# FM-Radio_180828.net
KiCad netlist of a schematic drawn in EAGLE
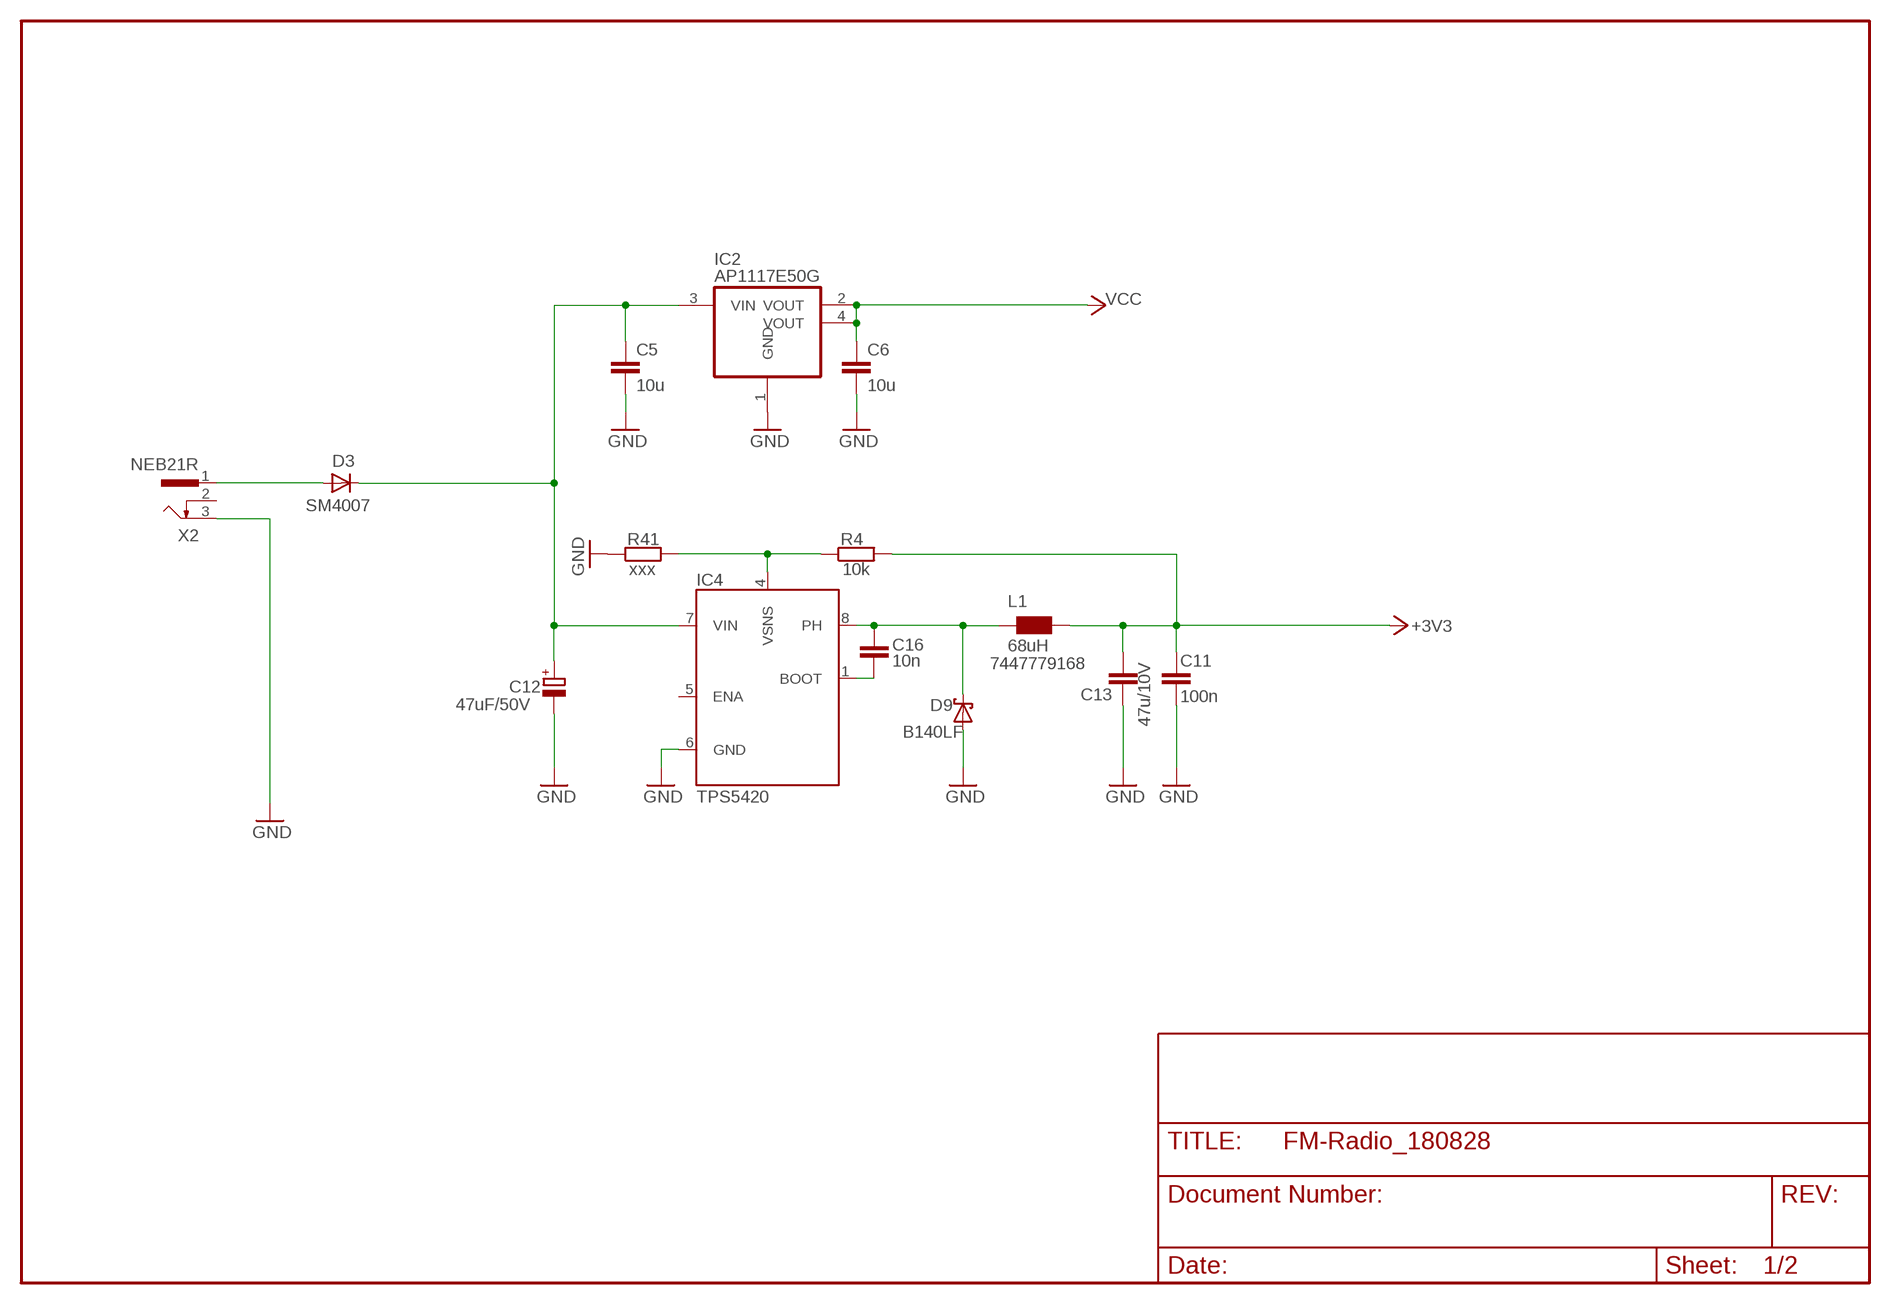
[diagram p0: schematic, sheet 1]
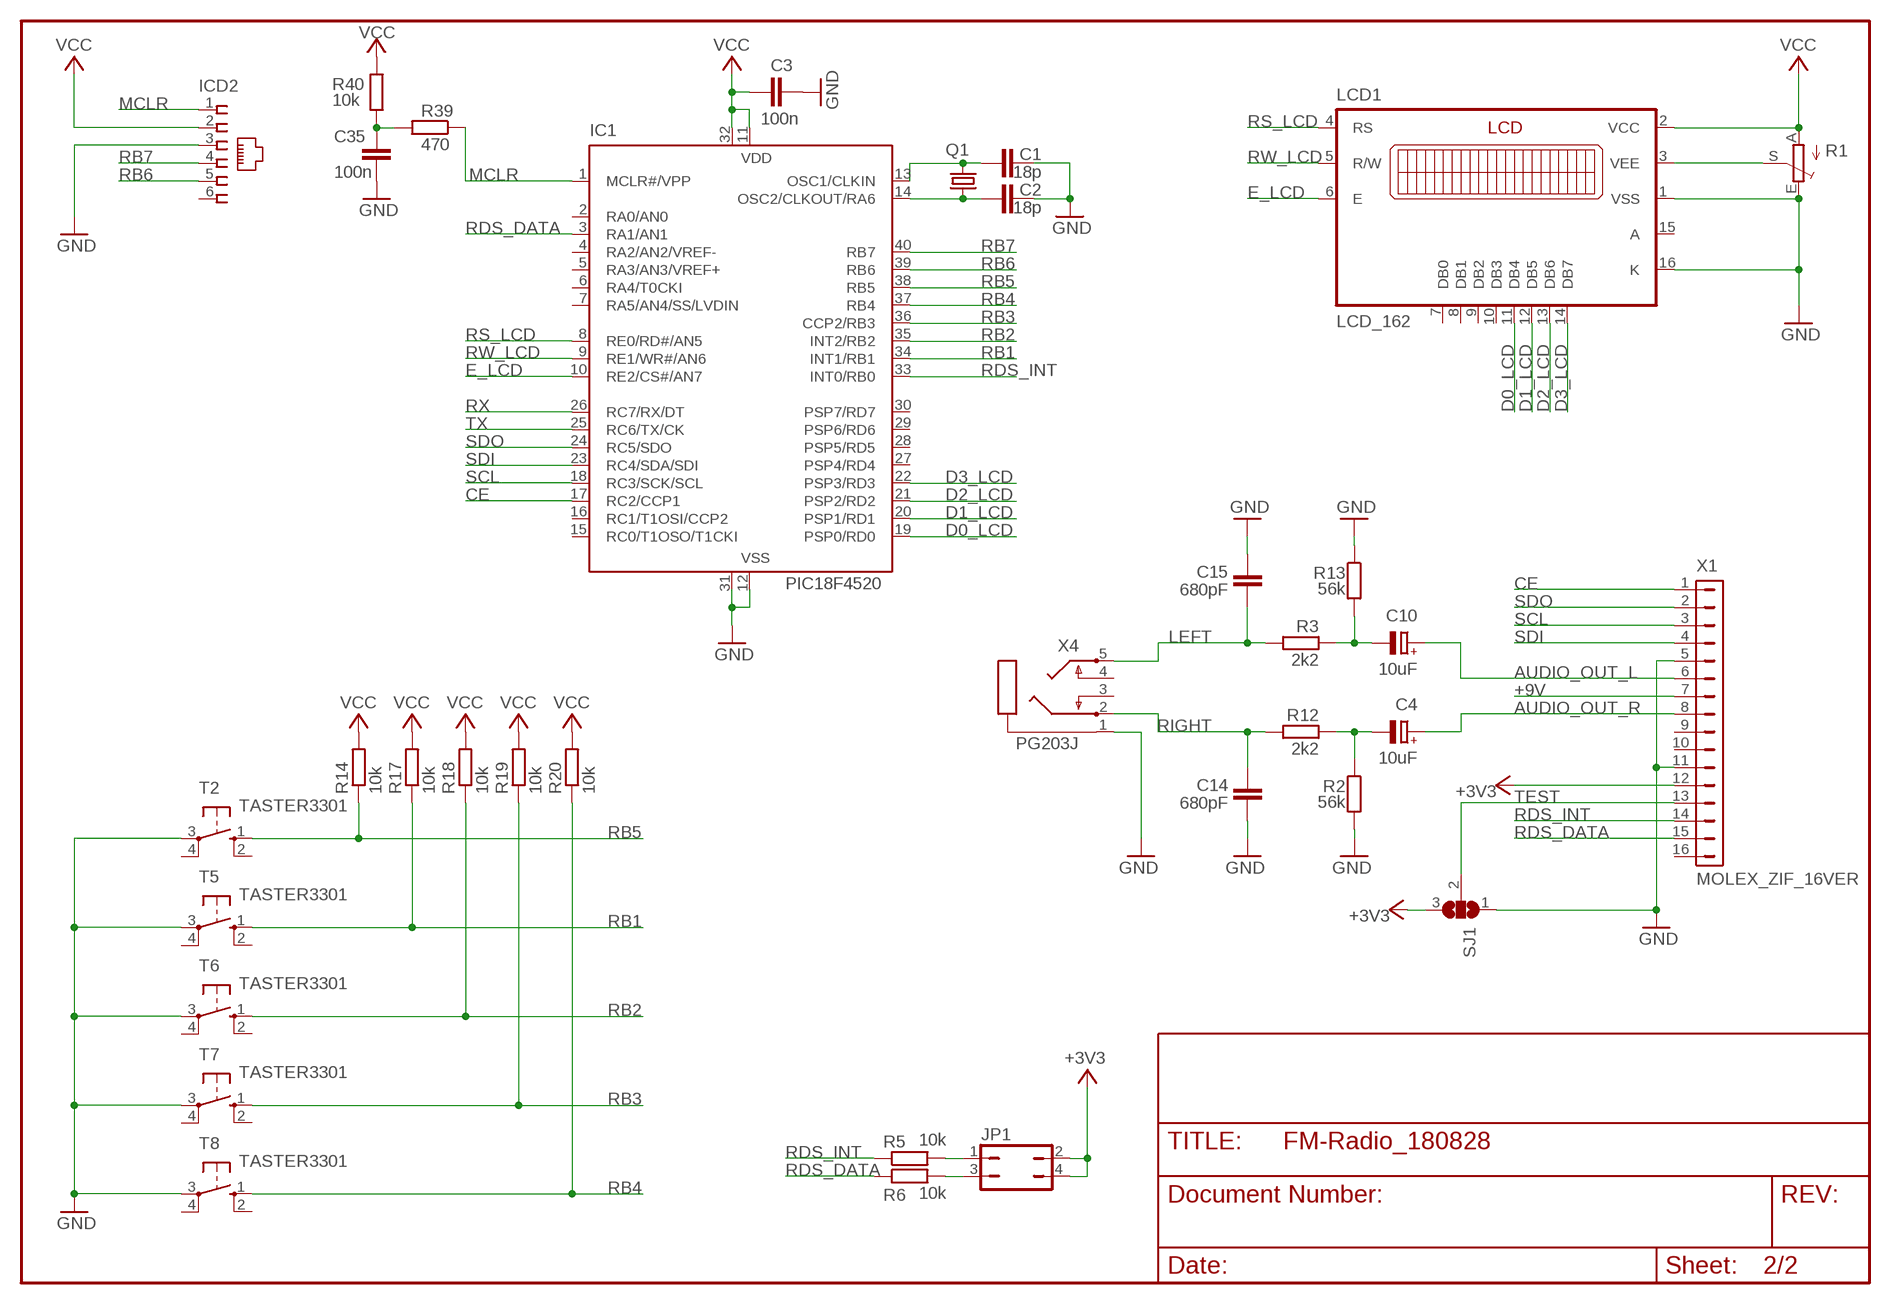
[diagram p1: schematic, sheet 2]

(export (version "E")
  (design (tool "Eeschema 10.0.6"))
  (components
    (comp (ref "C1")
      (value "18p")
      (footprint "eagle-import:C0805")
      (libsource (lib "eagle-import") (part "C-EUC0805"))
    )
    (comp (ref "C2")
      (value "18p")
      (footprint "eagle-import:C0805")
      (libsource (lib "eagle-import") (part "C-EUC0805"))
    )
    (comp (ref "C3")
      (value "100n")
      (footprint "eagle-import:C0805")
      (libsource (lib "eagle-import") (part "C-EUC0805"))
    )
    (comp (ref "C4")
      (value "10uF")
      (footprint "eagle-import:TT2D4")
      (libsource (lib "eagle-import") (part "CPOL-EUTT2D4"))
    )
    (comp (ref "C10")
      (value "10uF")
      (footprint "eagle-import:TT2D4")
      (libsource (lib "eagle-import") (part "CPOL-EUTT2D4"))
    )
    (comp (ref "C14")
      (value "680pF")
      (footprint "eagle-import:C025-025X050")
      (libsource (lib "eagle-import") (part "C-EU025-025X050"))
    )
    (comp (ref "C15")
      (value "680pF")
      (footprint "eagle-import:C025-025X050")
      (libsource (lib "eagle-import") (part "C-EU025-025X050"))
    )
    (comp (ref "C35")
      (value "100n")
      (footprint "eagle-import:C0805")
      (libsource (lib "eagle-import") (part "C-EUC0805"))
    )
    (comp (ref "IC1")
      (value "PIC18F4520")
      (footprint "eagle-import:DIL40")
      (libsource (lib "eagle-import") (part "PIC18C4X2"))
    )
    (comp (ref "ICD2")
      (value "520250-3")
      (footprint "eagle-import:520250-3")
      (libsource (lib "eagle-import") (part "520250-3"))
    )
    (comp (ref "JP1")
      (value "JP2Q")
      (footprint "eagle-import:JP2Q")
      (libsource (lib "eagle-import") (part "JP2Q"))
    )
    (comp (ref "LCD1")
      (value "LCD_162")
      (footprint "eagle-import:LCD_162")
      (libsource (lib "eagle-import") (part "LCD_162"))
    )
    (comp (ref "Q1")
      (value "CRYTALHC49U-V")
      (footprint "eagle-import:HC49U-V")
      (libsource (lib "eagle-import") (part "CRYTALHC49U-V"))
    )
    (comp (ref "R1")
      (value "TRIM_EU-LI10")
      (footprint "eagle-import:LI10")
      (libsource (lib "eagle-import") (part "TRIM_EU-LI10"))
    )
    (comp (ref "R2")
      (value "56k")
      (footprint "eagle-import:0207_7")
      (libsource (lib "eagle-import") (part "R-EU_0207/7"))
    )
    (comp (ref "R3")
      (value "2k2")
      (footprint "eagle-import:0207_7")
      (libsource (lib "eagle-import") (part "R-EU_0207/7"))
    )
    (comp (ref "R5")
      (value "10k")
      (footprint "eagle-import:M0805")
      (libsource (lib "eagle-import") (part "rcl_416_R-EU_M0805"))
    )
    (comp (ref "R6")
      (value "10k")
      (footprint "eagle-import:M0805")
      (libsource (lib "eagle-import") (part "rcl_416_R-EU_M0805"))
    )
    (comp (ref "R12")
      (value "2k2")
      (footprint "eagle-import:0207_7")
      (libsource (lib "eagle-import") (part "R-EU_0207/7"))
    )
    (comp (ref "R13")
      (value "56k")
      (footprint "eagle-import:0207_7")
      (libsource (lib "eagle-import") (part "R-EU_0207/7"))
    )
    (comp (ref "R14")
      (value "10k")
      (footprint "eagle-import:0207_7")
      (libsource (lib "eagle-import") (part "R-EU_0207/7"))
    )
    (comp (ref "R17")
      (value "10k")
      (footprint "eagle-import:0207_7")
      (libsource (lib "eagle-import") (part "R-EU_0207/7"))
    )
    (comp (ref "R18")
      (value "10k")
      (footprint "eagle-import:0207_7")
      (libsource (lib "eagle-import") (part "R-EU_0207/7"))
    )
    (comp (ref "R19")
      (value "10k")
      (footprint "eagle-import:0207_7")
      (libsource (lib "eagle-import") (part "R-EU_0207/7"))
    )
    (comp (ref "R20")
      (value "10k")
      (footprint "eagle-import:0207_7")
      (libsource (lib "eagle-import") (part "R-EU_0207/7"))
    )
    (comp (ref "R39")
      (value "470")
      (footprint "eagle-import:M0805")
      (libsource (lib "eagle-import") (part "R-EU_M0805"))
    )
    (comp (ref "R40")
      (value "10k")
      (footprint "eagle-import:M0805")
      (libsource (lib "eagle-import") (part "R-EU_M0805"))
    )
    (comp (ref "SJ1")
      (value "SJ2W")
      (footprint "eagle-import:SJ_2")
      (libsource (lib "eagle-import") (part "SJ2W"))
    )
    (comp (ref "T2")
      (value "TASTER3301")
      (footprint "eagle-import:TASTER3301")
      (libsource (lib "eagle-import") (part "TASTER3301"))
    )
    (comp (ref "T5")
      (value "TASTER3301")
      (footprint "eagle-import:TASTER3301")
      (libsource (lib "eagle-import") (part "TASTER3301"))
    )
    (comp (ref "T6")
      (value "TASTER3301")
      (footprint "eagle-import:TASTER3301")
      (libsource (lib "eagle-import") (part "TASTER3301"))
    )
    (comp (ref "T7")
      (value "TASTER3301")
      (footprint "eagle-import:TASTER3301")
      (libsource (lib "eagle-import") (part "TASTER3301"))
    )
    (comp (ref "T8")
      (value "TASTER3301")
      (footprint "eagle-import:TASTER3301")
      (libsource (lib "eagle-import") (part "TASTER3301"))
    )
    (comp (ref "X1")
      (value "MOLEX_ZIF_16VER")
      (footprint "eagle-import:ZIF_16POL")
      (libsource (lib "eagle-import") (part "MOLEX_ZIF_16VER"))
    )
    (comp (ref "X4")
      (value "PG203J")
      (footprint "eagle-import:PG203J")
      (libsource (lib "eagle-import") (part "PG203J"))
    )
    (comp (ref "C5")
      (value "10u")
      (footprint "eagle-import:C0805")
      (libsource (lib "eagle-import") (part "C-EUC0805"))
    )
    (comp (ref "C6")
      (value "10u")
      (footprint "eagle-import:C0805")
      (libsource (lib "eagle-import") (part "C-EUC0805"))
    )
    (comp (ref "C11")
      (value "100n")
      (footprint "eagle-import:C0805")
      (libsource (lib "eagle-import") (part "rcl_416_C-EUC0805"))
    )
    (comp (ref "C12")
      (value "47uF/50V")
      (footprint "eagle-import:PANASONIC_D")
      (libsource (lib "eagle-import") (part "rcl_416_CPOL-EUD"))
    )
    (comp (ref "C13")
      (value "47u/10V")
      (footprint "eagle-import:C1210")
      (libsource (lib "eagle-import") (part "C-EUC1210"))
    )
    (comp (ref "C16")
      (value "10n")
      (footprint "eagle-import:C0805")
      (libsource (lib "eagle-import") (part "rcl_416_C-EUC0805"))
    )
    (comp (ref "D3")
      (value "SM4007")
      (footprint "eagle-import:MELF")
      (libsource (lib "eagle-import") (part "DIODE_MELF"))
    )
    (comp (ref "D9")
      (value "B140LF")
      (footprint "eagle-import:CD1607")
      (libsource (lib "eagle-import") (part "SCHOTTKY_CD1607"))
    )
    (comp (ref "IC2")
      (value "AP1117E50G")
      (footprint "eagle-import:SOT223")
      (libsource (lib "eagle-import") (part "REG1117-2OUT"))
    )
    (comp (ref "IC4")
      (value "TPS5420")
      (footprint "eagle-import:SO8")
      (libsource (lib "eagle-import") (part "TPS5410"))
    )
    (comp (ref "L1")
      (value "68uH")
      (footprint "eagle-import:WE-PD_S_M")
      (libsource (lib "eagle-import") (part "WE-PD_S/M"))
    )
    (comp (ref "R4")
      (value "10k")
      (footprint "eagle-import:R0805")
      (libsource (lib "eagle-import") (part "R-EU_R0805"))
    )
    (comp (ref "R41")
      (value "xxx")
      (footprint "eagle-import:R0805")
      (libsource (lib "eagle-import") (part "R-EU_R0805"))
    )
    (comp (ref "X2")
      (value "NEB21R")
      (footprint "eagle-import:NEB21R")
      (fields (field (name "MPN") "NEB 21 R"))
      (libsource (lib "eagle-import") (part "NEB21R"))
    )
  )
  (nets
    (net (code "1") (name "+3V3") (class "Default")
      (node (ref "C11") (pin "1") (pinfunction "1_1") (pintype "passive"))
      (node (ref "C13") (pin "1") (pinfunction "1_1") (pintype "passive"))
      (node (ref "JP1") (pin "2") (pinfunction "2_2") (pintype "passive"))
      (node (ref "JP1") (pin "4") (pinfunction "4_4") (pintype "passive"))
      (node (ref "L1") (pin "1") (pinfunction "2_1") (pintype "passive"))
      (node (ref "R4") (pin "2") (pinfunction "2_2") (pintype "passive"))
      (node (ref "SJ1") (pin "3") (pinfunction "3_3") (pintype "passive"))
      (node (ref "X1") (pin "12") (pinfunction "12_12") (pintype "passive"))
    )
    (net (code "2") (name "+9V") (class "Default")
      (node (ref "C12") (pin "+") (pinfunction "+_+") (pintype "passive"))
      (node (ref "C5") (pin "1") (pinfunction "1_1") (pintype "passive"))
      (node (ref "D3") (pin "C") (pinfunction "C_C") (pintype "passive"))
      (node (ref "IC2") (pin "3") (pinfunction "VIN_3") (pintype "input"))
      (node (ref "IC4") (pin "7") (pinfunction "VIN_7") (pintype "bidirectional"))
      (node (ref "X1") (pin "7") (pinfunction "7_7") (pintype "passive"))
    )
    (net (code "3") (name "AUDIO_OUT_L") (class "Default")
      (node (ref "C10") (pin "+") (pinfunction "+_+") (pintype "passive"))
      (node (ref "X1") (pin "6") (pinfunction "6_6") (pintype "passive"))
    )
    (net (code "4") (name "AUDIO_OUT_R") (class "Default")
      (node (ref "C4") (pin "+") (pinfunction "+_+") (pintype "passive"))
      (node (ref "X1") (pin "8") (pinfunction "8_8") (pintype "passive"))
    )
    (net (code "5") (name "CE") (class "Default")
      (node (ref "IC1") (pin "17") (pinfunction "RC2/CCP1_17") (pintype "bidirectional"))
      (node (ref "X1") (pin "1") (pinfunction "1_1") (pintype "passive"))
    )
    (net (code "6") (name "D0_LCD") (class "Default")
      (node (ref "IC1") (pin "19") (pinfunction "PSP0/RD0_19") (pintype "bidirectional"))
      (node (ref "LCD1") (pin "11") (pinfunction "DB4_11") (pintype "passive"))
    )
    (net (code "7") (name "D1_LCD") (class "Default")
      (node (ref "IC1") (pin "20") (pinfunction "PSP1/RD1_20") (pintype "bidirectional"))
      (node (ref "LCD1") (pin "12") (pinfunction "DB5_12") (pintype "passive"))
    )
    (net (code "8") (name "D2_LCD") (class "Default")
      (node (ref "IC1") (pin "21") (pinfunction "PSP2/RD2_21") (pintype "bidirectional"))
      (node (ref "LCD1") (pin "13") (pinfunction "DB6_13") (pintype "passive"))
    )
    (net (code "9") (name "D3_LCD") (class "Default")
      (node (ref "IC1") (pin "22") (pinfunction "PSP3/RD3_22") (pintype "bidirectional"))
      (node (ref "LCD1") (pin "14") (pinfunction "DB7_14") (pintype "passive"))
    )
    (net (code "10") (name "E_LCD") (class "Default")
      (node (ref "IC1") (pin "10") (pinfunction "RE2/CS#/AN7_10") (pintype "bidirectional"))
      (node (ref "LCD1") (pin "6") (pinfunction "E_6") (pintype "input"))
    )
    (net (code "11") (name "GND") (class "Default")
      (node (ref "C1") (pin "2") (pinfunction "2_2") (pintype "passive"))
      (node (ref "C11") (pin "2") (pinfunction "2_2") (pintype "passive"))
      (node (ref "C12") (pin "-") (pinfunction "-_-") (pintype "passive"))
      (node (ref "C13") (pin "2") (pinfunction "2_2") (pintype "passive"))
      (node (ref "C14") (pin "1") (pinfunction "1_1") (pintype "passive"))
      (node (ref "C15") (pin "2") (pinfunction "2_2") (pintype "passive"))
      (node (ref "C2") (pin "2") (pinfunction "2_2") (pintype "passive"))
      (node (ref "C3") (pin "2") (pinfunction "2_2") (pintype "passive"))
      (node (ref "C35") (pin "2") (pinfunction "2_2") (pintype "passive"))
      (node (ref "C5") (pin "2") (pinfunction "2_2") (pintype "passive"))
      (node (ref "C6") (pin "2") (pinfunction "2_2") (pintype "passive"))
      (node (ref "D9") (pin "A") (pinfunction "A_A") (pintype "passive"))
      (node (ref "IC1") (pin "12") (pinfunction "VSS_12") (pintype "power_in"))
      (node (ref "IC1") (pin "31") (pinfunction "VSS_31") (pintype "power_in"))
      (node (ref "IC2") (pin "1") (pinfunction "GND_1") (pintype "power_in"))
      (node (ref "IC4") (pin "6") (pinfunction "GND_6") (pintype "bidirectional"))
      (node (ref "ICD2") (pin "3") (pinfunction "3_3") (pintype "passive"))
      (node (ref "LCD1") (pin "1") (pinfunction "VSS_1") (pintype "power_in"))
      (node (ref "LCD1") (pin "16") (pinfunction "K_16") (pintype "input"))
      (node (ref "R1") (pin "E") (pinfunction "E_E") (pintype "passive"))
      (node (ref "R13") (pin "1") (pinfunction "1_1") (pintype "passive"))
      (node (ref "R2") (pin "2") (pinfunction "2_2") (pintype "passive"))
      (node (ref "R41") (pin "1") (pinfunction "1_1") (pintype "passive"))
      (node (ref "SJ1") (pin "1") (pinfunction "1_1") (pintype "passive"))
      (node (ref "T2") (pin "3") (pinfunction "P_3") (pintype "passive"))
      (node (ref "T5") (pin "3") (pinfunction "P_3") (pintype "passive"))
      (node (ref "T6") (pin "3") (pinfunction "P_3") (pintype "passive"))
      (node (ref "T7") (pin "3") (pinfunction "P_3") (pintype "passive"))
      (node (ref "T8") (pin "3") (pinfunction "P_3") (pintype "passive"))
      (node (ref "X1") (pin "11") (pinfunction "11_11") (pintype "passive"))
      (node (ref "X1") (pin "5") (pinfunction "5_5") (pintype "passive"))
      (node (ref "X2") (pin "3") (pinfunction "3_3") (pintype "passive"))
      (node (ref "X4") (pin "1") (pinfunction "1_1") (pintype "passive"))
    )
    (net (code "12") (name "LEFT") (class "Default")
      (node (ref "C15") (pin "1") (pinfunction "1_1") (pintype "passive"))
      (node (ref "R3") (pin "1") (pinfunction "1_1") (pintype "passive"))
      (node (ref "X4") (pin "5") (pinfunction "5_5") (pintype "passive"))
    )
    (net (code "13") (name "MCLR") (class "Default")
      (node (ref "IC1") (pin "1") (pinfunction "MCLR#/VPP_1") (pintype "input"))
      (node (ref "ICD2") (pin "1") (pinfunction "1_1") (pintype "passive"))
      (node (ref "R39") (pin "1") (pinfunction "1_1") (pintype "passive"))
    )
    (net (code "14") (name "Net-(C4-Pad-)") (class "Default")
      (node (ref "C4") (pin "-") (pinfunction "-_-") (pintype "passive"))
      (node (ref "R12") (pin "2") (pinfunction "2_2") (pintype "passive"))
      (node (ref "R2") (pin "1") (pinfunction "1_1") (pintype "passive"))
    )
    (net (code "15") (name "Net-(C10-Pad-)") (class "Default")
      (node (ref "C10") (pin "-") (pinfunction "-_-") (pintype "passive"))
      (node (ref "R13") (pin "2") (pinfunction "2_2") (pintype "passive"))
      (node (ref "R3") (pin "2") (pinfunction "2_2") (pintype "passive"))
    )
    (net (code "16") (name "Net-(C35-Pad1)") (class "Default")
      (node (ref "C35") (pin "1") (pinfunction "1_1") (pintype "passive"))
      (node (ref "R39") (pin "2") (pinfunction "2_2") (pintype "passive"))
      (node (ref "R40") (pin "2") (pinfunction "2_2") (pintype "passive"))
    )
    (net (code "17") (name "Net-(D3-PadA)") (class "Default")
      (node (ref "D3") (pin "A") (pinfunction "A_A") (pintype "passive"))
      (node (ref "X2") (pin "1") (pinfunction "1_1") (pintype "passive"))
    )
    (net (code "18") (name "Net-(IC1-OSC1{slash}CLKIN)") (class "Default")
      (node (ref "C1") (pin "1") (pinfunction "1_1") (pintype "passive"))
      (node (ref "IC1") (pin "13") (pinfunction "OSC1/CLKIN_13") (pintype "input"))
      (node (ref "Q1") (pin "2") (pinfunction "2_2") (pintype "passive"))
    )
    (net (code "19") (name "Net-(IC1-OSC2{slash}CLKOUT{slash}RA6)") (class "Default")
      (node (ref "C2") (pin "1") (pinfunction "1_1") (pintype "passive"))
      (node (ref "IC1") (pin "14") (pinfunction "OSC2/CLKOUT/RA6_14") (pintype "output"))
      (node (ref "Q1") (pin "1") (pinfunction "1_1") (pintype "passive"))
    )
    (net (code "20") (name "Net-(IC4-BOOT)") (class "Default")
      (node (ref "C16") (pin "1") (pinfunction "1_1") (pintype "passive"))
      (node (ref "IC4") (pin "1") (pinfunction "BOOT_1") (pintype "bidirectional"))
    )
    (net (code "21") (name "Net-(IC4-PH)") (class "Default")
      (node (ref "C16") (pin "2") (pinfunction "2_2") (pintype "passive"))
      (node (ref "D9") (pin "C") (pinfunction "C_C") (pintype "passive"))
      (node (ref "IC4") (pin "8") (pinfunction "PH_8") (pintype "bidirectional"))
      (node (ref "L1") (pin "2") (pinfunction "1_2") (pintype "passive"))
    )
    (net (code "22") (name "Net-(IC4-VSNS)") (class "Default")
      (node (ref "IC4") (pin "4") (pinfunction "VSNS_4") (pintype "bidirectional"))
      (node (ref "R4") (pin "1") (pinfunction "1_1") (pintype "passive"))
      (node (ref "R41") (pin "2") (pinfunction "2_2") (pintype "passive"))
    )
    (net (code "23") (name "Net-(JP1-Pad1)") (class "Default")
      (node (ref "JP1") (pin "1") (pinfunction "1_1") (pintype "passive"))
      (node (ref "R5") (pin "2") (pinfunction "2_2") (pintype "passive"))
    )
    (net (code "24") (name "Net-(JP1-Pad3)") (class "Default")
      (node (ref "JP1") (pin "3") (pinfunction "3_3") (pintype "passive"))
      (node (ref "R6") (pin "2") (pinfunction "2_2") (pintype "passive"))
    )
    (net (code "25") (name "Net-(LCD1-VEE)") (class "Default")
      (node (ref "LCD1") (pin "3") (pinfunction "VEE_3") (pintype "power_in"))
      (node (ref "R1") (pin "S") (pinfunction "S_S") (pintype "passive"))
    )
    (net (code "26") (name "RB1") (class "Default")
      (node (ref "IC1") (pin "34") (pinfunction "INT1/RB1_34") (pintype "bidirectional"))
      (node (ref "R17") (pin "1") (pinfunction "1_1") (pintype "passive"))
      (node (ref "T5") (pin "1") (pinfunction "S_1") (pintype "passive"))
    )
    (net (code "27") (name "RB2") (class "Default")
      (node (ref "IC1") (pin "35") (pinfunction "INT2/RB2_35") (pintype "bidirectional"))
      (node (ref "R18") (pin "1") (pinfunction "1_1") (pintype "passive"))
      (node (ref "T6") (pin "1") (pinfunction "S_1") (pintype "passive"))
    )
    (net (code "28") (name "RB3") (class "Default")
      (node (ref "IC1") (pin "36") (pinfunction "CCP2/RB3_36") (pintype "bidirectional"))
      (node (ref "R19") (pin "1") (pinfunction "1_1") (pintype "passive"))
      (node (ref "T7") (pin "1") (pinfunction "S_1") (pintype "passive"))
    )
    (net (code "29") (name "RB4") (class "Default")
      (node (ref "IC1") (pin "37") (pinfunction "RB4_37") (pintype "bidirectional"))
      (node (ref "R20") (pin "1") (pinfunction "1_1") (pintype "passive"))
      (node (ref "T8") (pin "1") (pinfunction "S_1") (pintype "passive"))
    )
    (net (code "30") (name "RB5") (class "Default")
      (node (ref "IC1") (pin "38") (pinfunction "RB5_38") (pintype "bidirectional"))
      (node (ref "R14") (pin "1") (pinfunction "1_1") (pintype "passive"))
      (node (ref "T2") (pin "1") (pinfunction "S_1") (pintype "passive"))
    )
    (net (code "31") (name "RB6") (class "Default")
      (node (ref "IC1") (pin "39") (pinfunction "RB6_39") (pintype "bidirectional"))
      (node (ref "ICD2") (pin "5") (pinfunction "5_5") (pintype "passive"))
    )
    (net (code "32") (name "RB7") (class "Default")
      (node (ref "IC1") (pin "40") (pinfunction "RB7_40") (pintype "bidirectional"))
      (node (ref "ICD2") (pin "4") (pinfunction "4_4") (pintype "passive"))
    )
    (net (code "33") (name "RDS_DATA") (class "Default")
      (node (ref "IC1") (pin "3") (pinfunction "RA1/AN1_3") (pintype "bidirectional"))
      (node (ref "R6") (pin "1") (pinfunction "1_1") (pintype "passive"))
      (node (ref "X1") (pin "15") (pinfunction "15_15") (pintype "passive"))
    )
    (net (code "34") (name "RDS_INT") (class "Default")
      (node (ref "IC1") (pin "33") (pinfunction "INT0/RB0_33") (pintype "bidirectional"))
      (node (ref "R5") (pin "1") (pinfunction "1_1") (pintype "passive"))
      (node (ref "X1") (pin "14") (pinfunction "14_14") (pintype "passive"))
    )
    (net (code "35") (name "RIGHT") (class "Default")
      (node (ref "C14") (pin "2") (pinfunction "2_2") (pintype "passive"))
      (node (ref "R12") (pin "1") (pinfunction "1_1") (pintype "passive"))
      (node (ref "X4") (pin "2") (pinfunction "2_2") (pintype "passive"))
    )
    (net (code "36") (name "RS_LCD") (class "Default")
      (node (ref "IC1") (pin "8") (pinfunction "RE0/RD#/AN5_8") (pintype "bidirectional"))
      (node (ref "LCD1") (pin "4") (pinfunction "RS_4") (pintype "input"))
    )
    (net (code "37") (name "RW_LCD") (class "Default")
      (node (ref "IC1") (pin "9") (pinfunction "RE1/WR#/AN6_9") (pintype "bidirectional"))
      (node (ref "LCD1") (pin "5") (pinfunction "R/W_5") (pintype "input"))
    )
    (net (code "38") (name "RX") (class "Default")
      (node (ref "IC1") (pin "26") (pinfunction "RC7/RX/DT_26") (pintype "bidirectional"))
    )
    (net (code "39") (name "SCL") (class "Default")
      (node (ref "IC1") (pin "18") (pinfunction "RC3/SCK/SCL_18") (pintype "bidirectional"))
      (node (ref "X1") (pin "3") (pinfunction "3_3") (pintype "passive"))
    )
    (net (code "40") (name "SDI") (class "Default")
      (node (ref "IC1") (pin "23") (pinfunction "RC4/SDA/SDI_23") (pintype "bidirectional"))
      (node (ref "X1") (pin "4") (pinfunction "4_4") (pintype "passive"))
    )
    (net (code "41") (name "SDO") (class "Default")
      (node (ref "IC1") (pin "24") (pinfunction "RC5/SDO_24") (pintype "bidirectional"))
      (node (ref "X1") (pin "2") (pinfunction "2_2") (pintype "passive"))
    )
    (net (code "42") (name "TEST") (class "Default")
      (node (ref "SJ1") (pin "2") (pinfunction "2_2") (pintype "passive"))
      (node (ref "X1") (pin "13") (pinfunction "13_13") (pintype "passive"))
    )
    (net (code "43") (name "TX") (class "Default")
      (node (ref "IC1") (pin "25") (pinfunction "RC6/TX/CK_25") (pintype "bidirectional"))
    )
    (net (code "44") (name "VCC") (class "Default")
      (node (ref "C3") (pin "1") (pinfunction "1_1") (pintype "passive"))
      (node (ref "C6") (pin "1") (pinfunction "1_1") (pintype "passive"))
      (node (ref "IC1") (pin "11") (pinfunction "VDD_11") (pintype "power_in"))
      (node (ref "IC1") (pin "32") (pinfunction "VDD_32") (pintype "power_in"))
      (node (ref "IC2") (pin "2") (pinfunction "VOUT_2") (pintype "output"))
      (node (ref "IC2") (pin "4") (pinfunction "VOUT_4") (pintype "bidirectional"))
      (node (ref "ICD2") (pin "2") (pinfunction "2_2") (pintype "passive"))
      (node (ref "LCD1") (pin "2") (pinfunction "VCC_2") (pintype "power_in"))
      (node (ref "R1") (pin "A") (pinfunction "A_A") (pintype "passive"))
      (node (ref "R14") (pin "2") (pinfunction "2_2") (pintype "passive"))
      (node (ref "R17") (pin "2") (pinfunction "2_2") (pintype "passive"))
      (node (ref "R18") (pin "2") (pinfunction "2_2") (pintype "passive"))
      (node (ref "R19") (pin "2") (pinfunction "2_2") (pintype "passive"))
      (node (ref "R20") (pin "2") (pinfunction "2_2") (pintype "passive"))
      (node (ref "R40") (pin "1") (pinfunction "1_1") (pintype "passive"))
    )
    (net (code "45") (name "unconnected-(IC1-PSP4{slash}RD4-Pad27)") (class "Default")
      (node (ref "IC1") (pin "27") (pinfunction "PSP4/RD4_27") (pintype "bidirectional"))
    )
    (net (code "46") (name "unconnected-(IC1-PSP5{slash}RD5-Pad28)") (class "Default")
      (node (ref "IC1") (pin "28") (pinfunction "PSP5/RD5_28") (pintype "bidirectional"))
    )
    (net (code "47") (name "unconnected-(IC1-PSP6{slash}RD6-Pad29)") (class "Default")
      (node (ref "IC1") (pin "29") (pinfunction "PSP6/RD6_29") (pintype "bidirectional"))
    )
    (net (code "48") (name "unconnected-(IC1-PSP7{slash}RD7-Pad30)") (class "Default")
      (node (ref "IC1") (pin "30") (pinfunction "PSP7/RD7_30") (pintype "bidirectional"))
    )
    (net (code "49") (name "unconnected-(IC1-RA0{slash}AN0-Pad2)") (class "Default")
      (node (ref "IC1") (pin "2") (pinfunction "RA0/AN0_2") (pintype "bidirectional"))
    )
    (net (code "50") (name "unconnected-(IC1-RA2{slash}AN2{slash}VREF--Pad4)") (class "Default")
      (node (ref "IC1") (pin "4") (pinfunction "RA2/AN2/VREF-_4") (pintype "bidirectional"))
    )
    (net (code "51") (name "unconnected-(IC1-RA3{slash}AN3{slash}VREF+-Pad5)") (class "Default")
      (node (ref "IC1") (pin "5") (pinfunction "RA3/AN3/VREF+_5") (pintype "bidirectional"))
    )
    (net (code "52") (name "unconnected-(IC1-RA4{slash}T0CKI-Pad6)") (class "Default")
      (node (ref "IC1") (pin "6") (pinfunction "RA4/T0CKI_6") (pintype "bidirectional"))
    )
    (net (code "53") (name "unconnected-(IC1-RA5{slash}AN4{slash}SS{slash}LVDIN-Pad7)") (class "Default")
      (node (ref "IC1") (pin "7") (pinfunction "RA5/AN4/SS/LVDIN_7") (pintype "bidirectional"))
    )
    (net (code "54") (name "unconnected-(IC1-RC0{slash}T1OSO{slash}T1CKI-Pad15)") (class "Default")
      (node (ref "IC1") (pin "15") (pinfunction "RC0/T1OSO/T1CKI_15") (pintype "bidirectional"))
    )
    (net (code "55") (name "unconnected-(IC1-RC1{slash}T1OSI{slash}CCP2-Pad16)") (class "Default")
      (node (ref "IC1") (pin "16") (pinfunction "RC1/T1OSI/CCP2_16") (pintype "bidirectional"))
    )
    (net (code "56") (name "unconnected-(IC4-ENA-Pad5)") (class "Default")
      (node (ref "IC4") (pin "5") (pinfunction "ENA_5") (pintype "bidirectional"))
    )
    (net (code "57") (name "unconnected-(ICD2-Pad6)") (class "Default")
      (node (ref "ICD2") (pin "6") (pinfunction "6_6") (pintype "passive"))
    )
    (net (code "58") (name "unconnected-(LCD1-A-Pad15)") (class "Default")
      (node (ref "LCD1") (pin "15") (pinfunction "A_15") (pintype "input"))
    )
    (net (code "59") (name "unconnected-(LCD1-DB0-Pad7)") (class "Default")
      (node (ref "LCD1") (pin "7") (pinfunction "DB0_7") (pintype "passive"))
    )
    (net (code "60") (name "unconnected-(LCD1-DB1-Pad8)") (class "Default")
      (node (ref "LCD1") (pin "8") (pinfunction "DB1_8") (pintype "passive"))
    )
    (net (code "61") (name "unconnected-(LCD1-DB2-Pad9)") (class "Default")
      (node (ref "LCD1") (pin "9") (pinfunction "DB2_9") (pintype "passive"))
    )
    (net (code "62") (name "unconnected-(LCD1-DB3-Pad10)") (class "Default")
      (node (ref "LCD1") (pin "10") (pinfunction "DB3_10") (pintype "passive"))
    )
    (net (code "63") (name "unconnected-(T2-P1-Pad4)") (class "Default")
      (node (ref "T2") (pin "4") (pinfunction "P1_4") (pintype "passive"))
    )
    (net (code "64") (name "unconnected-(T2-S1-Pad2)") (class "Default")
      (node (ref "T2") (pin "2") (pinfunction "S1_2") (pintype "passive"))
    )
    (net (code "65") (name "unconnected-(T5-P1-Pad4)") (class "Default")
      (node (ref "T5") (pin "4") (pinfunction "P1_4") (pintype "passive"))
    )
    (net (code "66") (name "unconnected-(T5-S1-Pad2)") (class "Default")
      (node (ref "T5") (pin "2") (pinfunction "S1_2") (pintype "passive"))
    )
    (net (code "67") (name "unconnected-(T6-P1-Pad4)") (class "Default")
      (node (ref "T6") (pin "4") (pinfunction "P1_4") (pintype "passive"))
    )
    (net (code "68") (name "unconnected-(T6-S1-Pad2)") (class "Default")
      (node (ref "T6") (pin "2") (pinfunction "S1_2") (pintype "passive"))
    )
    (net (code "69") (name "unconnected-(T7-P1-Pad4)") (class "Default")
      (node (ref "T7") (pin "4") (pinfunction "P1_4") (pintype "passive"))
    )
    (net (code "70") (name "unconnected-(T7-S1-Pad2)") (class "Default")
      (node (ref "T7") (pin "2") (pinfunction "S1_2") (pintype "passive"))
    )
    (net (code "71") (name "unconnected-(T8-P1-Pad4)") (class "Default")
      (node (ref "T8") (pin "4") (pinfunction "P1_4") (pintype "passive"))
    )
    (net (code "72") (name "unconnected-(T8-S1-Pad2)") (class "Default")
      (node (ref "T8") (pin "2") (pinfunction "S1_2") (pintype "passive"))
    )
    (net (code "73") (name "unconnected-(X1-Pad9)") (class "Default")
      (node (ref "X1") (pin "9") (pinfunction "9_9") (pintype "passive"))
    )
    (net (code "74") (name "unconnected-(X1-Pad10)") (class "Default")
      (node (ref "X1") (pin "10") (pinfunction "10_10") (pintype "passive"))
    )
    (net (code "75") (name "unconnected-(X1-Pad16)") (class "Default")
      (node (ref "X1") (pin "16") (pinfunction "16_16") (pintype "passive"))
    )
    (net (code "76") (name "unconnected-(X2-Pad2)") (class "Default")
      (node (ref "X2") (pin "2") (pinfunction "2_2") (pintype "passive"))
    )
    (net (code "77") (name "unconnected-(X4-Pad3)") (class "Default")
      (node (ref "X4") (pin "3") (pinfunction "3_3") (pintype "passive"))
    )
    (net (code "78") (name "unconnected-(X4-Pad4)") (class "Default")
      (node (ref "X4") (pin "4") (pinfunction "4_4") (pintype "passive"))
    )
  )
)
